# Lumiboard_-_main_board__rev_B.net
KiCad netlist of a schematic drawn in EAGLE
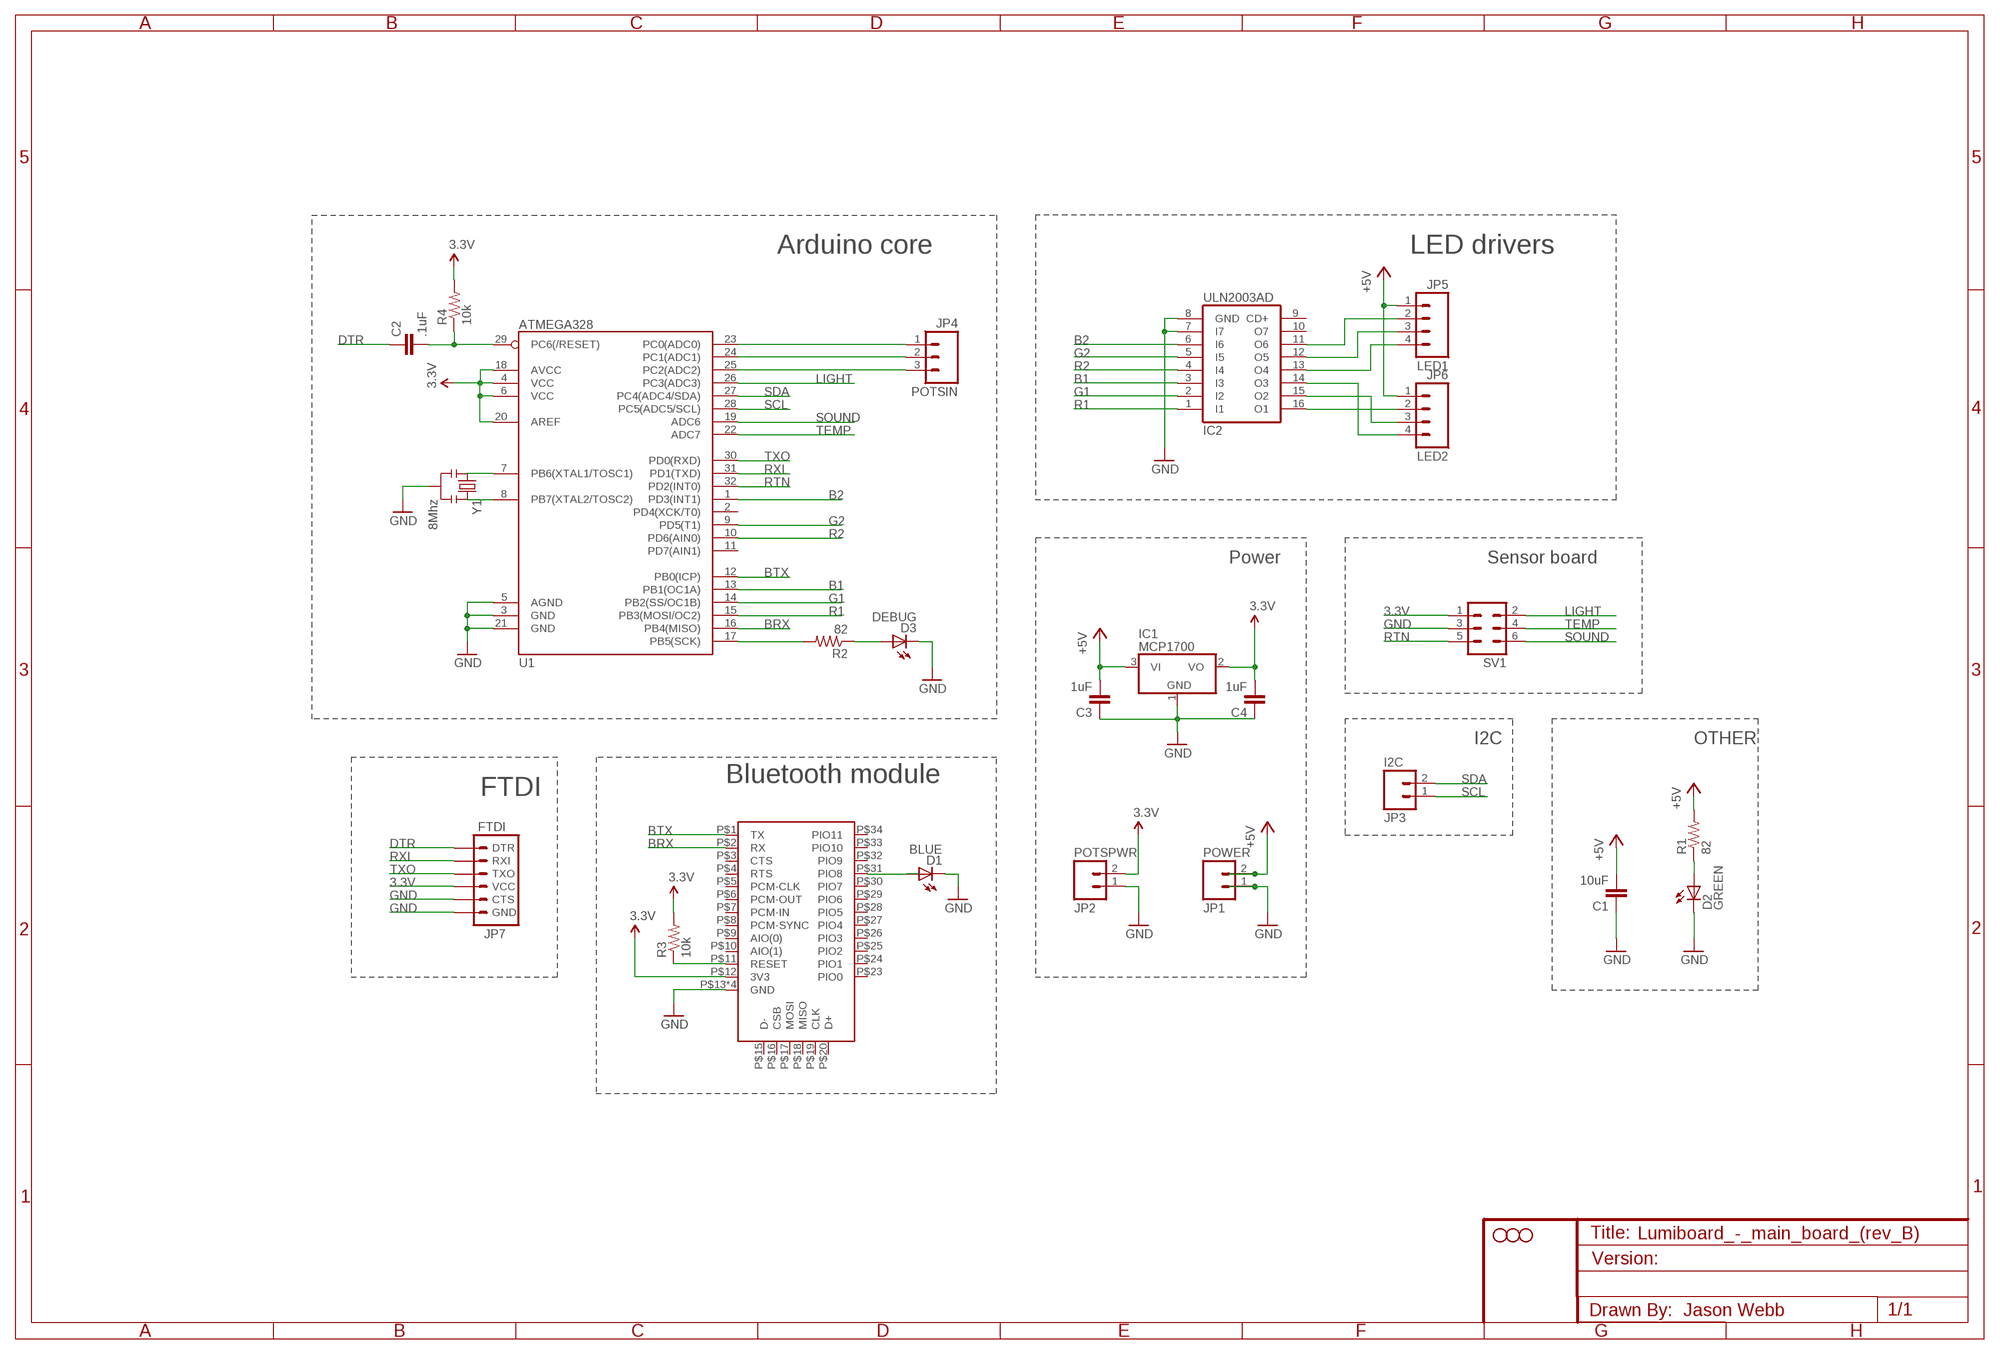
[diagram p0: schematic, sheet 1]

(export (version "E")
  (design (tool "Eeschema 10.0.6"))
  (components
    (comp (ref "C1")
      (value "10uF")
      (footprint "eagle-import:0805")
      (libsource (lib "eagle-import") (part "CAP0805"))
    )
    (comp (ref "C2")
      (value ".1uF")
      (footprint "eagle-import:0805")
      (libsource (lib "eagle-import") (part "CAP0805"))
    )
    (comp (ref "C3")
      (value "1uF")
      (footprint "eagle-import:0805")
      (libsource (lib "eagle-import") (part "CAP0805"))
    )
    (comp (ref "C4")
      (value "1uF")
      (footprint "eagle-import:0805")
      (libsource (lib "eagle-import") (part "CAP0805"))
    )
    (comp (ref "D1")
      (value "BLUE")
      (footprint "eagle-import:CHIPLED_0805")
      (libsource (lib "eagle-import") (part "LEDCHIPLED_0805"))
    )
    (comp (ref "D2")
      (value "GREEN")
      (footprint "eagle-import:CHIPLED_0805")
      (libsource (lib "eagle-import") (part "LEDCHIPLED_0805"))
    )
    (comp (ref "D3")
      (value "DEBUG")
      (footprint "eagle-import:CHIPLED_0805")
      (libsource (lib "eagle-import") (part "LEDCHIPLED_0805"))
    )
    (comp (ref "I2C")
      (value "JP3")
      (footprint "eagle-import:1X02")
      (libsource (lib "eagle-import") (part "M02PTH"))
    )
    (comp (ref "IC1")
      (value "MCP1700")
      (footprint "eagle-import:SOT23")
      (libsource (lib "eagle-import") (part "MCP1703CB"))
    )
    (comp (ref "IC2")
      (value "ULN2003AD")
      (footprint "eagle-import:SO16")
      (libsource (lib "eagle-import") (part "ULN2003AD"))
    )
    (comp (ref "JP2")
      (value "STAND-OFFTIGHT")
      (footprint "eagle-import:STAND-OFF-TIGHT")
      (libsource (lib "eagle-import") (part "STAND-OFFTIGHT"))
    )
    (comp (ref "JP4")
      (value "STAND-OFFTIGHT")
      (footprint "eagle-import:STAND-OFF-TIGHT")
      (libsource (lib "eagle-import") (part "STAND-OFFTIGHT"))
    )
    (comp (ref "JP5")
      (value "STAND-OFFTIGHT")
      (footprint "eagle-import:STAND-OFF-TIGHT")
      (libsource (lib "eagle-import") (part "STAND-OFFTIGHT"))
    )
    (comp (ref "JP7")
      (value "FTDI")
      (footprint "eagle-import:1X06_LOCK")
      (libsource (lib "eagle-import") (part "ARDUINO_SERIAL_PROGRAMLOCK"))
    )
    (comp (ref "LED1")
      (value "JP5")
      (footprint "eagle-import:1X04")
      (libsource (lib "eagle-import") (part "M04PTH"))
    )
    (comp (ref "LED2")
      (value "JP6")
      (footprint "eagle-import:1X04")
      (libsource (lib "eagle-import") (part "M04PTH"))
    )
    (comp (ref "POTSIN")
      (value "JP4")
      (footprint "eagle-import:1X03")
      (libsource (lib "eagle-import") (part "M03PTH"))
    )
    (comp (ref "POTSPWR")
      (value "JP2")
      (footprint "eagle-import:1X02")
      (libsource (lib "eagle-import") (part "M02PTH"))
    )
    (comp (ref "POWER")
      (value "JP1")
      (footprint "eagle-import:1X02")
      (libsource (lib "eagle-import") (part "M02PTH"))
    )
    (comp (ref "R1")
      (value "82")
      (footprint "eagle-import:R0805")
      (libsource (lib "eagle-import") (part "R-US_R0805"))
    )
    (comp (ref "R2")
      (value "82")
      (footprint "eagle-import:R0805")
      (libsource (lib "eagle-import") (part "R-US_R0805"))
    )
    (comp (ref "R3")
      (value "10k")
      (footprint "eagle-import:R0805")
      (libsource (lib "eagle-import") (part "R-US_R0805"))
    )
    (comp (ref "R4")
      (value "10k")
      (footprint "eagle-import:R0805")
      (libsource (lib "eagle-import") (part "R-US_R0805"))
    )
    (comp (ref "SV1")
      (value "ML6")
      (footprint "eagle-import:ML6")
      (libsource (lib "eagle-import") (part "ML6"))
    )
    (comp (ref "U1")
      (value "ATMEGA328")
      (footprint "eagle-import:TQFP32-08")
      (libsource (lib "eagle-import") (part "ATMEGA168"))
    )
    (comp (ref "U2")
      (value "DX_BT_MODULE")
      (footprint "eagle-import:DXBLUETOOTHMODULE")
      (libsource (lib "eagle-import") (part "DX_BT_MODULE"))
    )
    (comp (ref "Y1")
      (value "8Mhz")
      (footprint "eagle-import:RESONATOR-SMD")
      (libsource (lib "eagle-import") (part "RESONATORSMD"))
    )
  )
  (nets
    (net (code "1") (name "+5V") (class "Default")
      (node (ref "C1") (pin "2") (pinfunction "2_2") (pintype "passive"))
      (node (ref "C3") (pin "2") (pinfunction "2_2") (pintype "passive"))
      (node (ref "IC1") (pin "3") (pinfunction "VI_3") (pintype "input"))
      (node (ref "LED1") (pin "1") (pinfunction "1_1") (pintype "passive"))
      (node (ref "LED2") (pin "1") (pinfunction "1_1") (pintype "passive"))
      (node (ref "POWER") (pin "2") (pinfunction "2_2") (pintype "passive"))
      (node (ref "R1") (pin "2") (pinfunction "2_2") (pintype "passive"))
    )
    (net (code "2") (name "/B1") (class "Default")
      (node (ref "IC2") (pin "3") (pinfunction "I3_3") (pintype "input"))
      (node (ref "U1") (pin "13") (pinfunction "PB1(OC1A)_13") (pintype "bidirectional"))
    )
    (net (code "3") (name "/B2") (class "Default")
      (node (ref "IC2") (pin "6") (pinfunction "I6_6") (pintype "input"))
      (node (ref "U1") (pin "1") (pinfunction "PD3(INT1)_1") (pintype "bidirectional"))
    )
    (net (code "4") (name "/BRX") (class "Default")
      (node (ref "U1") (pin "16") (pinfunction "PB4(MISO)_16") (pintype "bidirectional"))
      (node (ref "U2") (pin "P$2") (pinfunction "RX_P$2") (pintype "input"))
    )
    (net (code "5") (name "/BTX") (class "Default")
      (node (ref "U1") (pin "12") (pinfunction "PB0(ICP)_12") (pintype "bidirectional"))
      (node (ref "U2") (pin "P$1") (pinfunction "TX_P$1") (pintype "output"))
    )
    (net (code "6") (name "/DTR") (class "Default")
      (node (ref "C2") (pin "1") (pinfunction "1_1") (pintype "passive"))
      (node (ref "JP7") (pin "1") (pinfunction "DTR_1") (pintype "passive"))
    )
    (net (code "7") (name "/G1") (class "Default")
      (node (ref "IC2") (pin "2") (pinfunction "I2_2") (pintype "input"))
      (node (ref "U1") (pin "14") (pinfunction "PB2(SS/OC1B)_14") (pintype "bidirectional"))
    )
    (net (code "8") (name "/G2") (class "Default")
      (node (ref "IC2") (pin "5") (pinfunction "I5_5") (pintype "input"))
      (node (ref "U1") (pin "9") (pinfunction "PD5(T1)_9") (pintype "bidirectional"))
    )
    (net (code "9") (name "/LIGHT") (class "Default")
      (node (ref "SV1") (pin "2") (pinfunction "2_2") (pintype "passive"))
      (node (ref "U1") (pin "26") (pinfunction "PC3(ADC3)_26") (pintype "bidirectional"))
    )
    (net (code "10") (name "/R1") (class "Default")
      (node (ref "IC2") (pin "1") (pinfunction "I1_1") (pintype "input"))
      (node (ref "U1") (pin "15") (pinfunction "PB3(MOSI/OC2)_15") (pintype "bidirectional"))
    )
    (net (code "11") (name "/R2") (class "Default")
      (node (ref "IC2") (pin "4") (pinfunction "I4_4") (pintype "input"))
      (node (ref "U1") (pin "10") (pinfunction "PD6(AIN0)_10") (pintype "bidirectional"))
    )
    (net (code "12") (name "/RTN") (class "Default")
      (node (ref "SV1") (pin "5") (pinfunction "5_5") (pintype "passive"))
      (node (ref "U1") (pin "32") (pinfunction "PD2(INT0)_32") (pintype "bidirectional"))
    )
    (net (code "13") (name "/RXI") (class "Default")
      (node (ref "JP7") (pin "2") (pinfunction "RXI_2") (pintype "passive"))
      (node (ref "U1") (pin "31") (pinfunction "PD1(TXD)_31") (pintype "bidirectional"))
    )
    (net (code "14") (name "/SCL") (class "Default")
      (node (ref "I2C") (pin "1") (pinfunction "1_1") (pintype "passive"))
      (node (ref "U1") (pin "28") (pinfunction "PC5(ADC5/SCL)_28") (pintype "bidirectional"))
    )
    (net (code "15") (name "/SDA") (class "Default")
      (node (ref "I2C") (pin "2") (pinfunction "2_2") (pintype "passive"))
      (node (ref "U1") (pin "27") (pinfunction "PC4(ADC4/SDA)_27") (pintype "bidirectional"))
    )
    (net (code "16") (name "/SOUND") (class "Default")
      (node (ref "SV1") (pin "6") (pinfunction "6_6") (pintype "passive"))
      (node (ref "U1") (pin "19") (pinfunction "ADC6_19") (pintype "bidirectional"))
    )
    (net (code "17") (name "/TEMP") (class "Default")
      (node (ref "SV1") (pin "4") (pinfunction "4_4") (pintype "passive"))
      (node (ref "U1") (pin "22") (pinfunction "ADC7_22") (pintype "bidirectional"))
    )
    (net (code "18") (name "/TXO") (class "Default")
      (node (ref "JP7") (pin "3") (pinfunction "TXO_3") (pintype "passive"))
      (node (ref "U1") (pin "30") (pinfunction "PD0(RXD)_30") (pintype "bidirectional"))
    )
    (net (code "19") (name "3.3V") (class "Default")
      (node (ref "C4") (pin "2") (pinfunction "2_2") (pintype "passive"))
      (node (ref "IC1") (pin "2") (pinfunction "VO_2") (pintype "passive"))
      (node (ref "JP7") (pin "4") (pinfunction "VCC_4") (pintype "passive"))
      (node (ref "POTSPWR") (pin "2") (pinfunction "2_2") (pintype "passive"))
      (node (ref "R3") (pin "2") (pinfunction "2_2") (pintype "passive"))
      (node (ref "R4") (pin "2") (pinfunction "2_2") (pintype "passive"))
      (node (ref "SV1") (pin "1") (pinfunction "1_1") (pintype "passive"))
      (node (ref "U1") (pin "18") (pinfunction "AVCC_18") (pintype "bidirectional"))
      (node (ref "U1") (pin "20") (pinfunction "AREF_20") (pintype "bidirectional"))
      (node (ref "U1") (pin "4") (pinfunction "VCC_4") (pintype "bidirectional"))
      (node (ref "U1") (pin "6") (pinfunction "VCC_6") (pintype "bidirectional"))
      (node (ref "U2") (pin "P$12") (pinfunction "3V3_P$12") (pintype "power_in"))
    )
    (net (code "20") (name "GND") (class "Default")
      (node (ref "C1") (pin "1") (pinfunction "1_1") (pintype "passive"))
      (node (ref "C3") (pin "1") (pinfunction "1_1") (pintype "passive"))
      (node (ref "C4") (pin "1") (pinfunction "1_1") (pintype "passive"))
      (node (ref "D1") (pin "C") (pinfunction "C_C") (pintype "passive"))
      (node (ref "D2") (pin "C") (pinfunction "C_C") (pintype "passive"))
      (node (ref "D3") (pin "C") (pinfunction "C_C") (pintype "passive"))
      (node (ref "IC1") (pin "1") (pinfunction "GND_1") (pintype "passive"))
      (node (ref "IC2") (pin "7") (pinfunction "I7_7") (pintype "input"))
      (node (ref "IC2") (pin "8") (pinfunction "GND_8") (pintype "power_in"))
      (node (ref "JP7") (pin "5") (pinfunction "CTS_5") (pintype "passive"))
      (node (ref "JP7") (pin "6") (pinfunction "GND_6") (pintype "passive"))
      (node (ref "POTSPWR") (pin "1") (pinfunction "1_1") (pintype "passive"))
      (node (ref "POWER") (pin "1") (pinfunction "1_1") (pintype "passive"))
      (node (ref "SV1") (pin "3") (pinfunction "3_3") (pintype "passive"))
      (node (ref "U1") (pin "21") (pinfunction "GND_21") (pintype "bidirectional"))
      (node (ref "U1") (pin "3") (pinfunction "GND_3") (pintype "bidirectional"))
      (node (ref "U1") (pin "5") (pinfunction "AGND_5") (pintype "bidirectional"))
      (node (ref "U2") (pin "P$13") (pinfunction "GND_P$13") (pintype "power_in"))
      (node (ref "U2") (pin "P$14") (pinfunction "GND_P$14") (pintype "power_in"))
      (node (ref "U2") (pin "P$21") (pinfunction "GND_P$21") (pintype "power_in"))
      (node (ref "U2") (pin "P$22") (pinfunction "GND_P$22") (pintype "power_in"))
      (node (ref "Y1") (pin "2") (pinfunction "2_2") (pintype "passive"))
    )
    (net (code "21") (name "Net-(D2-PadA)") (class "Default")
      (node (ref "D2") (pin "A") (pinfunction "A_A") (pintype "passive"))
      (node (ref "R1") (pin "1") (pinfunction "1_1") (pintype "passive"))
    )
    (net (code "22") (name "Net-(D3-PadA)") (class "Default")
      (node (ref "D3") (pin "A") (pinfunction "A_A") (pintype "passive"))
      (node (ref "R2") (pin "1") (pinfunction "1_1") (pintype "passive"))
    )
    (net (code "23") (name "Net-(IC2-O1)") (class "Default")
      (node (ref "IC2") (pin "16") (pinfunction "O1_16") (pintype "open_collector"))
      (node (ref "LED2") (pin "2") (pinfunction "2_2") (pintype "passive"))
    )
    (net (code "24") (name "Net-(IC2-O2)") (class "Default")
      (node (ref "IC2") (pin "15") (pinfunction "O2_15") (pintype "open_collector"))
      (node (ref "LED2") (pin "3") (pinfunction "3_3") (pintype "passive"))
    )
    (net (code "25") (name "Net-(IC2-O3)") (class "Default")
      (node (ref "IC2") (pin "14") (pinfunction "O3_14") (pintype "open_collector"))
      (node (ref "LED2") (pin "4") (pinfunction "4_4") (pintype "passive"))
    )
    (net (code "26") (name "Net-(IC2-O4)") (class "Default")
      (node (ref "IC2") (pin "13") (pinfunction "O4_13") (pintype "open_collector"))
      (node (ref "LED1") (pin "4") (pinfunction "4_4") (pintype "passive"))
    )
    (net (code "27") (name "Net-(IC2-O5)") (class "Default")
      (node (ref "IC2") (pin "12") (pinfunction "O5_12") (pintype "open_collector"))
      (node (ref "LED1") (pin "3") (pinfunction "3_3") (pintype "passive"))
    )
    (net (code "28") (name "Net-(IC2-O6)") (class "Default")
      (node (ref "IC2") (pin "11") (pinfunction "O6_11") (pintype "open_collector"))
      (node (ref "LED1") (pin "2") (pinfunction "2_2") (pintype "passive"))
    )
    (net (code "29") (name "Net-(U1-PB5(SCK))") (class "Default")
      (node (ref "R2") (pin "2") (pinfunction "2_2") (pintype "passive"))
      (node (ref "U1") (pin "17") (pinfunction "PB5(SCK)_17") (pintype "bidirectional"))
    )
    (net (code "30") (name "Net-(U1-PB6(XTAL1{slash}TOSC1))") (class "Default")
      (node (ref "U1") (pin "7") (pinfunction "PB6(XTAL1/TOSC1)_7") (pintype "bidirectional"))
      (node (ref "Y1") (pin "1") (pinfunction "1_1") (pintype "passive"))
    )
    (net (code "31") (name "Net-(U1-PB7(XTAL2{slash}TOSC2))") (class "Default")
      (node (ref "U1") (pin "8") (pinfunction "PB7(XTAL2/TOSC2)_8") (pintype "bidirectional"))
      (node (ref "Y1") (pin "3") (pinfunction "3_3") (pintype "passive"))
    )
    (net (code "32") (name "Net-(U1-PC0(ADC0))") (class "Default")
      (node (ref "POTSIN") (pin "1") (pinfunction "1_1") (pintype "passive"))
      (node (ref "U1") (pin "23") (pinfunction "PC0(ADC0)_23") (pintype "bidirectional"))
    )
    (net (code "33") (name "Net-(U1-PC1(ADC1))") (class "Default")
      (node (ref "POTSIN") (pin "2") (pinfunction "2_2") (pintype "passive"))
      (node (ref "U1") (pin "24") (pinfunction "PC1(ADC1)_24") (pintype "bidirectional"))
    )
    (net (code "34") (name "Net-(U1-PC2(ADC2))") (class "Default")
      (node (ref "POTSIN") (pin "3") (pinfunction "3_3") (pintype "passive"))
      (node (ref "U1") (pin "25") (pinfunction "PC2(ADC2)_25") (pintype "bidirectional"))
    )
    (net (code "35") (name "Net-(U1-PC6({slash}RESET))") (class "Default")
      (node (ref "C2") (pin "2") (pinfunction "2_2") (pintype "passive"))
      (node (ref "R4") (pin "1") (pinfunction "1_1") (pintype "passive"))
      (node (ref "U1") (pin "29") (pinfunction "PC6(/RESET)_29") (pintype "bidirectional"))
    )
    (net (code "36") (name "Net-(U2-PIO8)") (class "Default")
      (node (ref "D1") (pin "A") (pinfunction "A_A") (pintype "passive"))
      (node (ref "U2") (pin "P$31") (pinfunction "PIO8_P$31") (pintype "bidirectional"))
    )
    (net (code "37") (name "Net-(U2-RESET)") (class "Default")
      (node (ref "R3") (pin "1") (pinfunction "1_1") (pintype "passive"))
      (node (ref "U2") (pin "P$11") (pinfunction "RESET_P$11") (pintype "input"))
    )
    (net (code "38") (name "unconnected-(IC2-CD+-Pad9)") (class "Default")
      (node (ref "IC2") (pin "9") (pinfunction "CD+_9") (pintype "passive"))
    )
    (net (code "39") (name "unconnected-(IC2-O7-Pad10)") (class "Default")
      (node (ref "IC2") (pin "10") (pinfunction "O7_10") (pintype "open_collector"))
    )
    (net (code "40") (name "unconnected-(U1-PD4(XCK{slash}T0)-Pad2)") (class "Default")
      (node (ref "U1") (pin "2") (pinfunction "PD4(XCK/T0)_2") (pintype "bidirectional"))
    )
    (net (code "41") (name "unconnected-(U1-PD7(AIN1)-Pad11)") (class "Default")
      (node (ref "U1") (pin "11") (pinfunction "PD7(AIN1)_11") (pintype "bidirectional"))
    )
    (net (code "42") (name "unconnected-(U2-AIO(0)-PadP$9)") (class "Default")
      (node (ref "U2") (pin "P$9") (pinfunction "AIO(0)_P$9") (pintype "bidirectional"))
    )
    (net (code "43") (name "unconnected-(U2-AIO(1)-PadP$10)") (class "Default")
      (node (ref "U2") (pin "P$10") (pinfunction "AIO(1)_P$10") (pintype "bidirectional"))
    )
    (net (code "44") (name "unconnected-(U2-CLK-PadP$19)") (class "Default")
      (node (ref "U2") (pin "P$19") (pinfunction "CLK_P$19") (pintype "input"))
    )
    (net (code "45") (name "unconnected-(U2-CSB-PadP$16)") (class "Default")
      (node (ref "U2") (pin "P$16") (pinfunction "CSB_P$16") (pintype "input"))
    )
    (net (code "46") (name "unconnected-(U2-CTS-PadP$3)") (class "Default")
      (node (ref "U2") (pin "P$3") (pinfunction "CTS_P$3") (pintype "input"))
    )
    (net (code "47") (name "unconnected-(U2-D+-PadP$20)") (class "Default")
      (node (ref "U2") (pin "P$20") (pinfunction "D+_P$20") (pintype "bidirectional"))
    )
    (net (code "48") (name "unconnected-(U2-D--PadP$15)") (class "Default")
      (node (ref "U2") (pin "P$15") (pinfunction "D-_P$15") (pintype "bidirectional"))
    )
    (net (code "49") (name "unconnected-(U2-MISO-PadP$18)") (class "Default")
      (node (ref "U2") (pin "P$18") (pinfunction "MISO_P$18") (pintype "output"))
    )
    (net (code "50") (name "unconnected-(U2-MOSI-PadP$17)") (class "Default")
      (node (ref "U2") (pin "P$17") (pinfunction "MOSI_P$17") (pintype "input"))
    )
    (net (code "51") (name "unconnected-(U2-PCM-CLK-PadP$5)") (class "Default")
      (node (ref "U2") (pin "P$5") (pinfunction "PCM-CLK_P$5") (pintype "bidirectional"))
    )
    (net (code "52") (name "unconnected-(U2-PCM-IN-PadP$7)") (class "Default")
      (node (ref "U2") (pin "P$7") (pinfunction "PCM-IN_P$7") (pintype "input"))
    )
    (net (code "53") (name "unconnected-(U2-PCM-OUT-PadP$6)") (class "Default")
      (node (ref "U2") (pin "P$6") (pinfunction "PCM-OUT_P$6") (pintype "output"))
    )
    (net (code "54") (name "unconnected-(U2-PCM-SYNC-PadP$8)") (class "Default")
      (node (ref "U2") (pin "P$8") (pinfunction "PCM-SYNC_P$8") (pintype "bidirectional"))
    )
    (net (code "55") (name "unconnected-(U2-PIO0-PadP$23)") (class "Default")
      (node (ref "U2") (pin "P$23") (pinfunction "PIO0_P$23") (pintype "bidirectional"))
    )
    (net (code "56") (name "unconnected-(U2-PIO1-PadP$24)") (class "Default")
      (node (ref "U2") (pin "P$24") (pinfunction "PIO1_P$24") (pintype "bidirectional"))
    )
    (net (code "57") (name "unconnected-(U2-PIO2-PadP$25)") (class "Default")
      (node (ref "U2") (pin "P$25") (pinfunction "PIO2_P$25") (pintype "bidirectional"))
    )
    (net (code "58") (name "unconnected-(U2-PIO3-PadP$26)") (class "Default")
      (node (ref "U2") (pin "P$26") (pinfunction "PIO3_P$26") (pintype "bidirectional"))
    )
    (net (code "59") (name "unconnected-(U2-PIO4-PadP$27)") (class "Default")
      (node (ref "U2") (pin "P$27") (pinfunction "PIO4_P$27") (pintype "bidirectional"))
    )
    (net (code "60") (name "unconnected-(U2-PIO5-PadP$28)") (class "Default")
      (node (ref "U2") (pin "P$28") (pinfunction "PIO5_P$28") (pintype "bidirectional"))
    )
    (net (code "61") (name "unconnected-(U2-PIO6-PadP$29)") (class "Default")
      (node (ref "U2") (pin "P$29") (pinfunction "PIO6_P$29") (pintype "bidirectional"))
    )
    (net (code "62") (name "unconnected-(U2-PIO7-PadP$30)") (class "Default")
      (node (ref "U2") (pin "P$30") (pinfunction "PIO7_P$30") (pintype "bidirectional"))
    )
    (net (code "63") (name "unconnected-(U2-PIO9-PadP$32)") (class "Default")
      (node (ref "U2") (pin "P$32") (pinfunction "PIO9_P$32") (pintype "bidirectional"))
    )
    (net (code "64") (name "unconnected-(U2-PIO10-PadP$33)") (class "Default")
      (node (ref "U2") (pin "P$33") (pinfunction "PIO10_P$33") (pintype "bidirectional"))
    )
    (net (code "65") (name "unconnected-(U2-PIO11-PadP$34)") (class "Default")
      (node (ref "U2") (pin "P$34") (pinfunction "PIO11_P$34") (pintype "bidirectional"))
    )
    (net (code "66") (name "unconnected-(U2-RTS-PadP$4)") (class "Default")
      (node (ref "U2") (pin "P$4") (pinfunction "RTS_P$4") (pintype "output"))
    )
  )
)
